# Encoder.net
KiCad netlist of a schematic drawn in Altium Designer
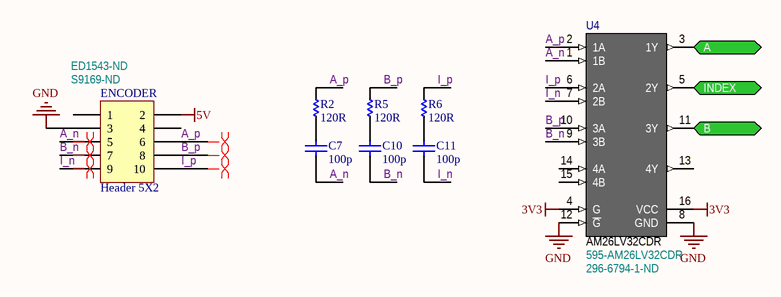
[diagram p0: Encoder.SchDoc]

(export (version "E")
  (design (tool "Eeschema 10.0.6"))
  (components
    (comp (ref "C7")
      (value "100p")
      (footprint "CAPC1608N")
      (description "Capacitor (Semiconductor SIM Model)")
      (fields (field (name "PUBLISHER") "Altium Limited"))
      (libsource (lib "Miscellaneous Devices") (part "Cap Semi"))
    )
    (comp (ref "C10")
      (value "100p")
      (footprint "CAPC1608N")
      (description "Capacitor (Semiconductor SIM Model)")
      (fields (field (name "PUBLISHER") "Altium Limited"))
      (libsource (lib "Miscellaneous Devices") (part "Cap Semi"))
    )
    (comp (ref "C11")
      (value "100p")
      (footprint "CAPC1608N")
      (description "Capacitor (Semiconductor SIM Model)")
      (fields (field (name "PUBLISHER") "Altium Limited"))
      (libsource (lib "Miscellaneous Devices") (part "Cap Semi"))
    )
    (comp (ref "ENCODER")
      (value "Header 5X2")
      (footprint "HDR2X5_SHROUDED")
      (description "Header, 5-Pin, Dual row")
      (fields
        (field (name "SUPPLIER PART NUMBER 1") "S9169-ND")
        (field (name "SUPPLIER PART NUMBER 2") "ED1543-ND")
        (field (name "PUBLISHER") "Altium Limited")
      )
      (libsource (lib "Miscellaneous Connectors") (part "Header 5X2"))
    )
    (comp (ref "R2")
      (value "120R")
      (footprint "RESC1608N")
      (description "Semiconductor Resistor")
      (fields (field (name "PUBLISHER") "Altium Limited"))
      (libsource (lib "Miscellaneous Devices") (part "Res Semi"))
    )
    (comp (ref "R5")
      (value "120R")
      (footprint "RESC1608N")
      (description "Semiconductor Resistor")
      (fields (field (name "PUBLISHER") "Altium Limited"))
      (libsource (lib "Miscellaneous Devices") (part "Res Semi"))
    )
    (comp (ref "R6")
      (value "120R")
      (footprint "RESC1608N")
      (description "Semiconductor Resistor")
      (fields (field (name "PUBLISHER") "Altium Limited"))
      (libsource (lib "Miscellaneous Devices") (part "Res Semi"))
    )
    (comp (ref "U4")
      (value "AM26LV32CDR")
      (footprint "SOIC127P600-16N")
      (description "Quad differential receiver")
      (fields
        (field (name "SUPPLIER PART NUMBER 1") "595-AM26LV32CDR")
        (field (name "SUPPLIER PART NUMBER 2") "296-6794-1-ND")
      )
      (libsource (lib "TI Drivers, Transmitters, Receivers") (part "AM26LV32CDR"))
    )
  )
  (nets
    (net (code "1") (name "/A") (class "Default")
      (node (ref "U4") (pin "3") (pinfunction "1Y_3") (pintype "output"))
    )
    (net (code "2") (name "/A_n") (class "Default")
      (node (ref "C7") (pin "1") (pinfunction "1_1") (pintype "passive"))
      (node (ref "ENCODER") (pin "5") (pinfunction "5_5") (pintype "passive"))
      (node (ref "U4") (pin "1") (pinfunction "1B_1") (pintype "input"))
    )
    (net (code "3") (name "/A_p") (class "Default")
      (node (ref "ENCODER") (pin "6") (pinfunction "6_6") (pintype "passive"))
      (node (ref "R2") (pin "2") (pinfunction "2_2") (pintype "passive"))
      (node (ref "U4") (pin "2") (pinfunction "1A_2") (pintype "input"))
    )
    (net (code "4") (name "/B") (class "Default")
      (node (ref "U4") (pin "11") (pinfunction "3Y_11") (pintype "output"))
    )
    (net (code "5") (name "/B_n") (class "Default")
      (node (ref "C10") (pin "1") (pinfunction "1_1") (pintype "passive"))
      (node (ref "ENCODER") (pin "7") (pinfunction "7_7") (pintype "passive"))
      (node (ref "U4") (pin "9") (pinfunction "3B_9") (pintype "input"))
    )
    (net (code "6") (name "/B_p") (class "Default")
      (node (ref "ENCODER") (pin "8") (pinfunction "8_8") (pintype "passive"))
      (node (ref "R5") (pin "2") (pinfunction "2_2") (pintype "passive"))
      (node (ref "U4") (pin "10") (pinfunction "3A_10") (pintype "input"))
    )
    (net (code "7") (name "/INDEX") (class "Default")
      (node (ref "U4") (pin "5") (pinfunction "2Y_5") (pintype "output"))
    )
    (net (code "8") (name "/I_n") (class "Default")
      (node (ref "C11") (pin "1") (pinfunction "1_1") (pintype "passive"))
      (node (ref "ENCODER") (pin "9") (pinfunction "9_9") (pintype "passive"))
      (node (ref "U4") (pin "7") (pinfunction "2B_7") (pintype "input"))
    )
    (net (code "9") (name "/I_p") (class "Default")
      (node (ref "ENCODER") (pin "10") (pinfunction "10_10") (pintype "passive"))
      (node (ref "R6") (pin "2") (pinfunction "2_2") (pintype "passive"))
      (node (ref "U4") (pin "6") (pinfunction "2A_6") (pintype "input"))
    )
    (net (code "10") (name "3V3") (class "Default")
      (node (ref "U4") (pin "16") (pinfunction "VCC_16") (pintype "power_in"))
      (node (ref "U4") (pin "4") (pinfunction "G_4") (pintype "input"))
    )
    (net (code "11") (name "5V") (class "Default")
      (node (ref "ENCODER") (pin "2") (pinfunction "2_2") (pintype "passive"))
    )
    (net (code "12") (name "GND") (class "Default")
      (node (ref "ENCODER") (pin "3") (pinfunction "3_3") (pintype "passive"))
      (node (ref "U4") (pin "12") (pinfunction "~{G}_12") (pintype "input"))
      (node (ref "U4") (pin "8") (pinfunction "GND_8") (pintype "power_in"))
    )
    (net (code "13") (name "Net-(C7-Pad2)") (class "Default")
      (node (ref "C7") (pin "2") (pinfunction "2_2") (pintype "passive"))
      (node (ref "R2") (pin "1") (pinfunction "1_1") (pintype "passive"))
    )
    (net (code "14") (name "Net-(C10-Pad2)") (class "Default")
      (node (ref "C10") (pin "2") (pinfunction "2_2") (pintype "passive"))
      (node (ref "R5") (pin "1") (pinfunction "1_1") (pintype "passive"))
    )
    (net (code "15") (name "Net-(C11-Pad2)") (class "Default")
      (node (ref "C11") (pin "2") (pinfunction "2_2") (pintype "passive"))
      (node (ref "R6") (pin "1") (pinfunction "1_1") (pintype "passive"))
    )
    (net (code "16") (name "unconnected-(ENCODER-Pad1)") (class "Default")
      (node (ref "ENCODER") (pin "1") (pinfunction "1_1") (pintype "passive"))
    )
    (net (code "17") (name "unconnected-(ENCODER-Pad4)") (class "Default")
      (node (ref "ENCODER") (pin "4") (pinfunction "4_4") (pintype "passive"))
    )
    (net (code "18") (name "unconnected-(U4-4A-Pad14)") (class "Default")
      (node (ref "U4") (pin "14") (pinfunction "4A_14") (pintype "input"))
    )
    (net (code "19") (name "unconnected-(U4-4B-Pad15)") (class "Default")
      (node (ref "U4") (pin "15") (pinfunction "4B_15") (pintype "input"))
    )
    (net (code "20") (name "unconnected-(U4-4Y-Pad13)") (class "Default")
      (node (ref "U4") (pin "13") (pinfunction "4Y_13") (pintype "output"))
    )
  )
)
